# StepUp_MT3608.net
KiCad netlist of a schematic drawn in Altium Designer
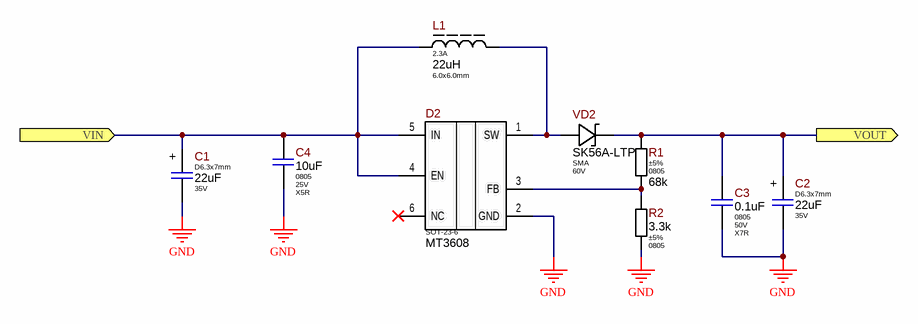
[diagram p0: StepUp_MT3608.SchDoc]

(export (version "E")
  (design (tool "Eeschema 10.0.6"))
  (components
    (comp (ref "C1")
      (value "22uF")
      (footprint "CAP-AE-PTH-63D05x70H10")
      (description "22uF 35V ±20% D6.3x7mm Low Leakage Aluminum Electrolytic Capacitor")
      (fields
        (field (name "PACKAGE") "D6.3x7mm")
        (field (name "VOLTAGE") "35V")
        (field (name "PART NUMBER") "KZL-035V220ME070-T/R")
        (field (name "MANUFACTURER") "Koshin")
      )
      (libsource (lib "capacitors") (part "KZL-035V220ME070-T/R"))
    )
    (comp (ref "C2")
      (value "22uF")
      (footprint "CAP-AE-PTH-63D05x70H10")
      (description "22uF 35V ±20% D6.3x7mm Low Leakage Aluminum Electrolytic Capacitor")
      (fields
        (field (name "PACKAGE") "D6.3x7mm")
        (field (name "VOLTAGE") "35V")
        (field (name "PART NUMBER") "KZL-035V220ME070-T/R")
        (field (name "MANUFACTURER") "Koshin")
      )
      (libsource (lib "capacitors") (part "KZL-035V220ME070-T/R"))
    )
    (comp (ref "C3")
      (value "0.1uF")
      (footprint "CAP-0805(2012)X85T10")
      (description "100nF 50V X7R ±10% 0805 Ceramic Capacitor RoHS")
      (fields
        (field (name "PACKAGE") "0805")
        (field (name "VOLTAGE") "50V")
        (field (name "DIELECTRIC TYPE") "X7R")
        (field (name "PART NUMBER") "CL21B104KBCNNNC")
        (field (name "MANUFACTURER") "Samsung Electro-Mechanics")
      )
      (libsource (lib "capacitors") (part "CL21B104KBCNNNC"))
    )
    (comp (ref "C4")
      (value "10uF")
      (footprint "CAP-0805(2012)X125T20")
      (description "10uF 25V X5R ±20% 0805 Ceramic Capacitor RoHS")
      (fields
        (field (name "PACKAGE") "0805")
        (field (name "VOLTAGE") "25V")
        (field (name "DIELECTRIC TYPE") "X5R")
        (field (name "PART NUMBER") "CL21A106KAYNNNG")
        (field (name "MANUFACTURER") "Samsung Electro-Mechanics")
      )
      (libsource (lib "capacitors") (part "CL21A106KAYNNNG"))
    )
    (comp (ref "D2")
      (value "MT3608")
      (footprint "MT3608_MED")
      (description "2V-24V Input High Efficiency 1.2MHz 2A Step Up Converter")
      (fields
        (field (name "PACKAGE") "SOT-23-6")
        (field (name "PART NUMBER") "MT3608")
        (field (name "MANUFACTURER") "Aerosemi")
      )
      (libsource (lib "ic") (part "MT3608"))
    )
    (comp (ref "L1")
      (value "22uH")
      (footprint "SRN6045TA-SERIES")
      (description "22uH Semi-Shielded Wirewound Inductor 2.3A 96mOhm")
      (fields
        (field (name "CURRENT") "2.3A")
        (field (name "PACKAGE") "6.0x6.0mm")
        (field (name "PART NUMBER") "SRN6045TA-220M")
        (field (name "TOLERANCE") "±20%")
      )
      (libsource (lib "inductors") (part "SRN6045TA-220M"))
    )
    (comp (ref "R1")
      (value "68k")
      (footprint "R_ANY_CHIP_0805_MED")
      (description "2.2 kOhms ±5% 1/8W 0805 Thick Film Resistor")
      (fields
        (field (name "TOLERANCE") "±5%")
        (field (name "PACKAGE") "0805")
        (field (name "PART NUMBER") "RC0805JR-072K2L")
        (field (name "MANUFACTURER") "Yageo")
      )
      (libsource (lib "resistors") (part "RC0805JR-072K2L"))
    )
    (comp (ref "R2")
      (value "3.3k")
      (footprint "R_ANY_CHIP_0805_MED")
      (description "3.3 kOhms ±5%, 1/8W 0805 Thick Film Resistor")
      (fields
        (field (name "TOLERANCE") "±5%")
        (field (name "PACKAGE") "0805")
        (field (name "PART NUMBER") "RC0805JR-073K3L")
        (field (name "MANUFACTURER") "Yageo")
      )
      (libsource (lib "resistors") (part "RC0805JR-073K3L"))
    )
    (comp (ref "VD2")
      (value "SK56A-LTP")
      (footprint "SMA_MED")
      (description "Diode Schottky 60V 5A, SMA")
      (fields
        (field (name "PART NUMBER") "SK56A-LTP")
        (field (name "PACKAGE") "SMA")
        (field (name "VOLTAGE") "60V")
        (field (name "MANUFACTURER") "Micro Commercial Components")
      )
      (libsource (lib "diodes") (part "SK56A-LTP"))
    )
  )
  (nets
    (net (code "1") (name "/VIN") (class "Default")
      (node (ref "C1") (pin "1") (pinfunction "1_1") (pintype "passive"))
      (node (ref "C4") (pin "1") (pinfunction "1_1") (pintype "passive"))
      (node (ref "D2") (pin "4") (pinfunction "EN_4") (pintype "passive"))
      (node (ref "D2") (pin "5") (pinfunction "IN_5") (pintype "passive"))
      (node (ref "L1") (pin "1") (pintype "passive"))
    )
    (net (code "2") (name "/VOUT") (class "Default")
      (node (ref "C2") (pin "1") (pinfunction "1_1") (pintype "passive"))
      (node (ref "C3") (pin "1") (pinfunction "1_1") (pintype "passive"))
      (node (ref "R1") (pin "1") (pintype "passive"))
      (node (ref "VD2") (pin "CA") (pintype "passive"))
    )
    (net (code "3") (name "GND") (class "Default")
      (node (ref "C1") (pin "2") (pinfunction "2_2") (pintype "passive"))
      (node (ref "C2") (pin "2") (pinfunction "2_2") (pintype "passive"))
      (node (ref "C3") (pin "2") (pinfunction "2_2") (pintype "passive"))
      (node (ref "C4") (pin "2") (pinfunction "2_2") (pintype "passive"))
      (node (ref "D2") (pin "2") (pinfunction "GND_2") (pintype "passive"))
      (node (ref "R2") (pin "2") (pintype "passive"))
    )
    (net (code "4") (name "Net-(D2-FB)") (class "Default")
      (node (ref "D2") (pin "3") (pinfunction "FB_3") (pintype "passive"))
      (node (ref "R1") (pin "2") (pintype "passive"))
      (node (ref "R2") (pin "1") (pintype "passive"))
    )
    (net (code "5") (name "Net-(D2-SW)") (class "Default")
      (node (ref "D2") (pin "1") (pinfunction "SW_1") (pintype "passive"))
      (node (ref "L1") (pin "2") (pintype "passive"))
      (node (ref "VD2") (pin "AN") (pintype "passive"))
    )
    (net (code "6") (name "unconnected-(D2-NC-Pad6)") (class "Default")
      (node (ref "D2") (pin "6") (pinfunction "NC_6") (pintype "passive+no_connect"))
    )
  )
)
